# LEDs.net
KiCad netlist of a schematic drawn in Altium Designer
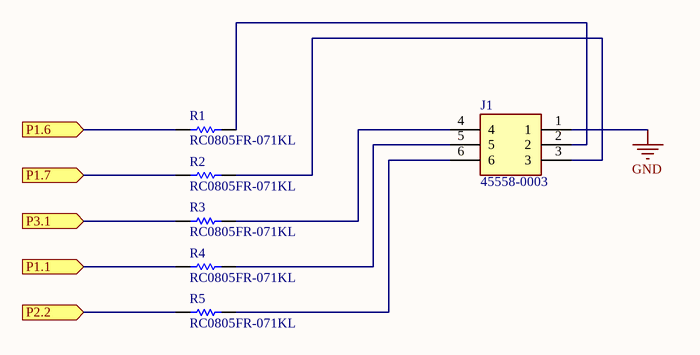
[diagram p0: LEDs.SchDoc]

(export (version "E")
  (design (tool "Eeschema 10.0.6"))
  (components
    (comp (ref "J1")
      (value "45558-0003")
      (footprint "SamacSys:455580003")
      (description "Connector")
      (fields (field (name "MOUSER PART NUMBER") "538-45558-0003"))
      (libsource (lib "*") (part "45558-0003"))
    )
    (comp (ref "R1")
      (value "RC0805FR-071KL")
      (footprint "RESC2013X60X35ML10T20")
      (description "Chip Resistor, 1 KOhm, +/- 1%, 125 mW, -55 to 155 degC, 0805 (2012 Metric), RoHS, Tape and Reel")
      (fields (field (name "TOLERANCE") "1%") (field (name "MANUFACTURER") "Yageo"))
      (libsource (lib "Altium Content Vault") (part "RES-2"))
    )
    (comp (ref "R2")
      (value "RC0805FR-071KL")
      (footprint "RESC2013X60X35ML10T20")
      (description "Chip Resistor, 1 KOhm, +/- 1%, 125 mW, -55 to 155 degC, 0805 (2012 Metric), RoHS, Tape and Reel")
      (fields (field (name "TOLERANCE") "1%") (field (name "MANUFACTURER") "Yageo"))
      (libsource (lib "Altium Content Vault") (part "RES-2"))
    )
    (comp (ref "R3")
      (value "RC0805FR-071KL")
      (footprint "RESC2013X60X35ML10T20")
      (description "Chip Resistor, 1 KOhm, +/- 1%, 125 mW, -55 to 155 degC, 0805 (2012 Metric), RoHS, Tape and Reel")
      (fields (field (name "TOLERANCE") "1%") (field (name "MANUFACTURER") "Yageo"))
      (libsource (lib "Altium Content Vault") (part "RES-2"))
    )
    (comp (ref "R4")
      (value "RC0805FR-071KL")
      (footprint "RESC2013X60X35ML10T20")
      (description "Chip Resistor, 1 KOhm, +/- 1%, 125 mW, -55 to 155 degC, 0805 (2012 Metric), RoHS, Tape and Reel")
      (fields (field (name "TOLERANCE") "1%") (field (name "MANUFACTURER") "Yageo"))
      (libsource (lib "Altium Content Vault") (part "RES-2"))
    )
    (comp (ref "R5")
      (value "RC0805FR-071KL")
      (footprint "RESC2013X60X35ML10T20")
      (description "Chip Resistor, 1 KOhm, +/- 1%, 125 mW, -55 to 155 degC, 0805 (2012 Metric), RoHS, Tape and Reel")
      (fields (field (name "TOLERANCE") "1%") (field (name "MANUFACTURER") "Yageo"))
      (libsource (lib "Altium Content Vault") (part "RES-2"))
    )
  )
  (nets
    (net (code "1") (name "/P1.1") (class "Default")
      (node (ref "R4") (pin "1") (pinfunction "1_1") (pintype "passive"))
    )
    (net (code "2") (name "/P1.6") (class "Default")
      (node (ref "R1") (pin "1") (pinfunction "1_1") (pintype "passive"))
    )
    (net (code "3") (name "/P1.7") (class "Default")
      (node (ref "R2") (pin "1") (pinfunction "1_1") (pintype "passive"))
    )
    (net (code "4") (name "/P2.2") (class "Default")
      (node (ref "R5") (pin "1") (pinfunction "1_1") (pintype "passive"))
    )
    (net (code "5") (name "/P3.1") (class "Default")
      (node (ref "R3") (pin "1") (pinfunction "1_1") (pintype "passive"))
    )
    (net (code "6") (name "GND") (class "Default")
      (node (ref "J1") (pin "1") (pinfunction "1_1") (pintype "passive"))
    )
    (net (code "7") (name "Net-(J1-Pad2)") (class "Default")
      (node (ref "J1") (pin "2") (pinfunction "2_2") (pintype "passive"))
      (node (ref "R1") (pin "2") (pinfunction "2_2") (pintype "passive"))
    )
    (net (code "8") (name "Net-(J1-Pad3)") (class "Default")
      (node (ref "J1") (pin "3") (pinfunction "3_3") (pintype "passive"))
      (node (ref "R2") (pin "2") (pinfunction "2_2") (pintype "passive"))
    )
    (net (code "9") (name "Net-(J1-Pad4)") (class "Default")
      (node (ref "J1") (pin "4") (pinfunction "4_4") (pintype "passive"))
      (node (ref "R3") (pin "2") (pinfunction "2_2") (pintype "passive"))
    )
    (net (code "10") (name "Net-(J1-Pad5)") (class "Default")
      (node (ref "J1") (pin "5") (pinfunction "5_5") (pintype "passive"))
      (node (ref "R4") (pin "2") (pinfunction "2_2") (pintype "passive"))
    )
    (net (code "11") (name "Net-(J1-Pad6)") (class "Default")
      (node (ref "J1") (pin "6") (pinfunction "6_6") (pintype "passive"))
      (node (ref "R5") (pin "2") (pinfunction "2_2") (pintype "passive"))
    )
  )
)
